# encoder-switch-type1-smd.net
KiCad netlist of a schematic drawn in EAGLE
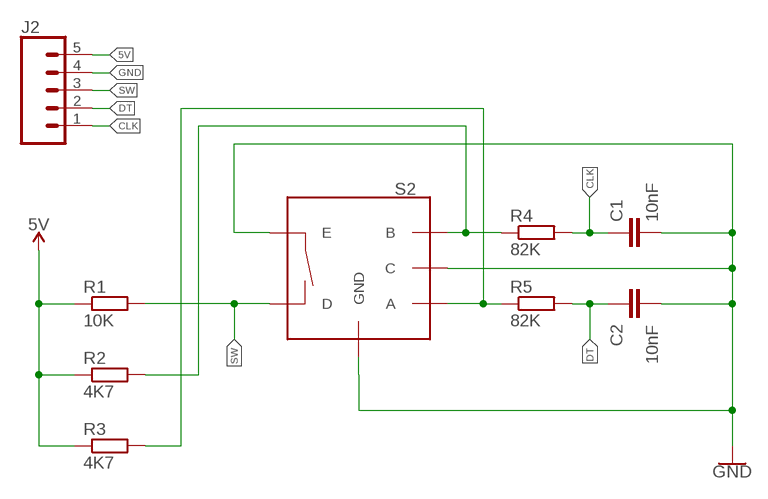
[diagram p0: schematic, sheet 1]

(export (version "E")
  (design (tool "Eeschema 10.0.6"))
  (components
    (comp (ref "C1")
      (value "10nF")
      (footprint "eagle-import:C1206")
      (libsource (lib "eagle-import") (part "C-EUC1206"))
    )
    (comp (ref "C2")
      (value "10nF")
      (footprint "eagle-import:C1206")
      (libsource (lib "eagle-import") (part "C-EUC1206"))
    )
    (comp (ref "J2")
      (value "CONN_051X05LA")
      (footprint "eagle-import:1X05_90")
      (libsource (lib "eagle-import") (part "CONN_051X05LA"))
    )
    (comp (ref "R1")
      (value "10K")
      (footprint "eagle-import:R1206")
      (libsource (lib "eagle-import") (part "R-EU_R1206"))
    )
    (comp (ref "R2")
      (value "4K7")
      (footprint "eagle-import:R1206")
      (libsource (lib "eagle-import") (part "R-EU_R1206"))
    )
    (comp (ref "R3")
      (value "4K7")
      (footprint "eagle-import:R1206")
      (libsource (lib "eagle-import") (part "R-EU_R1206"))
    )
    (comp (ref "R4")
      (value "82K")
      (footprint "eagle-import:R1206")
      (libsource (lib "eagle-import") (part "R-EU_R1206"))
    )
    (comp (ref "R5")
      (value "82K")
      (footprint "eagle-import:R1206")
      (libsource (lib "eagle-import") (part "R-EU_R1206"))
    )
    (comp (ref "S2")
      (value "ENCODER_SWITCH")
      (footprint "eagle-import:ROTARY_ENC_PLAIN")
      (libsource (lib "eagle-import") (part "ENCODER_SWITCH"))
    )
  )
  (nets
    (net (code "1") (name "5V") (class "Default")
      (node (ref "J2") (pin "5") (pinfunction "5_5") (pintype "passive"))
      (node (ref "R1") (pin "1") (pinfunction "1_1") (pintype "passive"))
      (node (ref "R2") (pin "1") (pinfunction "1_1") (pintype "passive"))
      (node (ref "R3") (pin "1") (pinfunction "1_1") (pintype "passive"))
    )
    (net (code "2") (name "CLK") (class "Default")
      (node (ref "C1") (pin "1") (pinfunction "1_1") (pintype "passive"))
      (node (ref "J2") (pin "1") (pinfunction "1_1") (pintype "passive"))
      (node (ref "R4") (pin "2") (pinfunction "2_2") (pintype "passive"))
    )
    (net (code "3") (name "DT") (class "Default")
      (node (ref "C2") (pin "1") (pinfunction "1_1") (pintype "passive"))
      (node (ref "J2") (pin "2") (pinfunction "2_2") (pintype "passive"))
      (node (ref "R5") (pin "2") (pinfunction "2_2") (pintype "passive"))
    )
    (net (code "4") (name "GND") (class "Default")
      (node (ref "C1") (pin "2") (pinfunction "2_2") (pintype "passive"))
      (node (ref "C2") (pin "2") (pinfunction "2_2") (pintype "passive"))
      (node (ref "J2") (pin "4") (pinfunction "4_4") (pintype "passive"))
      (node (ref "S2") (pin "C") (pinfunction "C_C") (pintype "bidirectional"))
      (node (ref "S2") (pin "E") (pinfunction "E_E") (pintype "bidirectional"))
      (node (ref "S2") (pin "GND1") (pinfunction "GND_GND1") (pintype "bidirectional"))
      (node (ref "S2") (pin "GND2") (pinfunction "GND_GND2") (pintype "bidirectional"))
    )
    (net (code "5") (name "Net-(R2-Pad2)") (class "Default")
      (node (ref "R2") (pin "2") (pinfunction "2_2") (pintype "passive"))
      (node (ref "R4") (pin "1") (pinfunction "1_1") (pintype "passive"))
      (node (ref "S2") (pin "B") (pinfunction "B_B") (pintype "bidirectional"))
    )
    (net (code "6") (name "Net-(R3-Pad2)") (class "Default")
      (node (ref "R3") (pin "2") (pinfunction "2_2") (pintype "passive"))
      (node (ref "R5") (pin "1") (pinfunction "1_1") (pintype "passive"))
      (node (ref "S2") (pin "A") (pinfunction "A_A") (pintype "bidirectional"))
    )
    (net (code "7") (name "SW") (class "Default")
      (node (ref "J2") (pin "3") (pinfunction "3_3") (pintype "passive"))
      (node (ref "R1") (pin "2") (pinfunction "2_2") (pintype "passive"))
      (node (ref "S2") (pin "D") (pinfunction "D_D") (pintype "bidirectional"))
    )
  )
)
